# arduinoHeader.net
KiCad netlist of a schematic drawn in Altium Designer
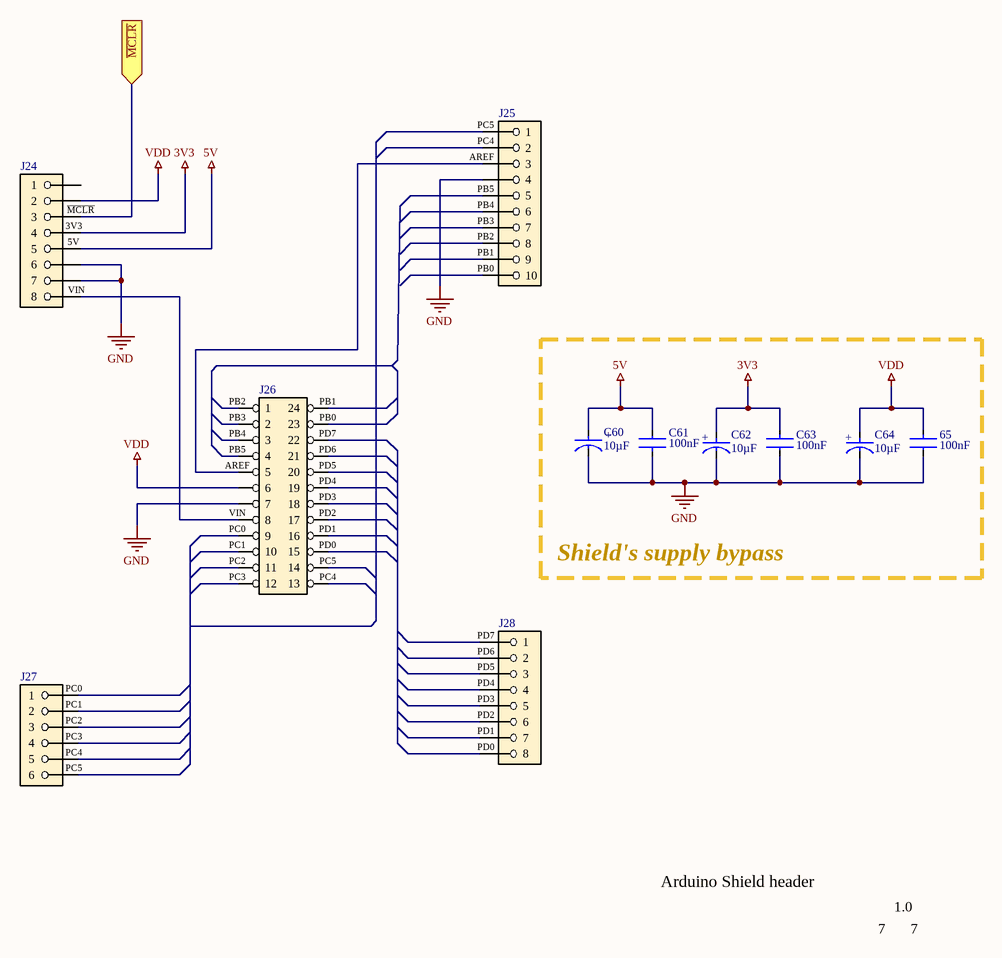
[diagram p0: arduinoHeader.SchDoc]

(export (version "E")
  (design (tool "Eeschema 10.0.6"))
  (components
    (comp (ref "65")
      (value "100nF")
      (footprint "FP-C0805C-DN-MFG")
      (description "CAP CER 1000PF 50V C0G/NP0 0805")
      (fields
        (field (name "MANUFACTURER") "KEMET")
        (field (name "OCTOPART") "https://octopart.com/c0805c102j5gactu-kemet-97757")
      )
      (libsource (lib "Altium Content Vault") (part "b4654b650e69147ec39a6b967a45e02"))
    )
    (comp (ref "C60")
      (value "F981C106MSAAS1")
      (footprint "FP-F98S-MFG")
      (description "CAP TANT 10UF 20% 16V 0805")
      (fields
        (field (name "TOLERANCE") "20%")
        (field (name "CAPACITANCE") "10µF")
        (field (name "OCTOPART") "https://octopart.com/f981c106msaas1-avx-49645945")
      )
      (libsource (lib "Altium Content Vault") (part "cf48714ba7e38822c1575c7ec0b6d1f"))
    )
    (comp (ref "C61")
      (value "100nF")
      (footprint "FP-C0805C-DN-MFG")
      (description "CAP CER 1000PF 50V C0G/NP0 0805")
      (fields
        (field (name "MANUFACTURER") "KEMET")
        (field (name "OCTOPART") "https://octopart.com/c0805c102j5gactu-kemet-97757")
      )
      (libsource (lib "Altium Content Vault") (part "b4654b650e69147ec39a6b967a45e02"))
    )
    (comp (ref "C62")
      (value "F981C106MSAAS1")
      (footprint "FP-F98S-MFG")
      (description "CAP TANT 10UF 20% 16V 0805")
      (fields
        (field (name "TOLERANCE") "20%")
        (field (name "CAPACITANCE") "10µF")
        (field (name "OCTOPART") "https://octopart.com/f981c106msaas1-avx-49645945")
      )
      (libsource (lib "Altium Content Vault") (part "cf48714ba7e38822c1575c7ec0b6d1f"))
    )
    (comp (ref "C63")
      (value "100nF")
      (footprint "FP-C0805C-DN-MFG")
      (description "CAP CER 1000PF 50V C0G/NP0 0805")
      (fields
        (field (name "MANUFACTURER") "KEMET")
        (field (name "OCTOPART") "https://octopart.com/c0805c102j5gactu-kemet-97757")
      )
      (libsource (lib "Altium Content Vault") (part "b4654b650e69147ec39a6b967a45e02"))
    )
    (comp (ref "C64")
      (value "F981C106MSAAS1")
      (footprint "FP-F98S-MFG")
      (description "CAP TANT 10UF 20% 16V 0805")
      (fields
        (field (name "TOLERANCE") "20%")
        (field (name "CAPACITANCE") "10µF")
        (field (name "OCTOPART") "https://octopart.com/f981c106msaas1-avx-49645945")
      )
      (libsource (lib "Altium Content Vault") (part "cf48714ba7e38822c1575c7ec0b6d1f"))
    )
    (comp (ref "J24")
      (value "Header 1x8 F")
      (footprint "Header 1x8")
      (libsource (lib "") (part "Header 1x8 F_1"))
    )
    (comp (ref "J25")
      (value "Header 1x10 F")
      (footprint "Header 1x10")
      (libsource (lib "goldpin") (part "Header 1x10 F"))
    )
    (comp (ref "J26")
      (value "Header 2x12")
      (footprint "Header 2x12")
      (libsource (lib "goldpin") (part "Header 2x12"))
    )
    (comp (ref "J27")
      (value "Header 1x6 F")
      (footprint "Header 1x6")
      (libsource (lib "goldpin") (part "Header 1x6 F"))
    )
    (comp (ref "J28")
      (value "Header 1x8 F")
      (footprint "Header 1x8")
      (libsource (lib "goldpin") (part "Header 1x8 F"))
    )
  )
  (nets
    (net (code "1") (name "/AREF") (class "Default")
      (node (ref "J25") (pin "3") (pinfunction "3_3") (pintype "passive"))
      (node (ref "J26") (pin "5") (pinfunction "5_5") (pintype "passive"))
    )
    (net (code "2") (name "/PB0") (class "Default")
      (node (ref "J25") (pin "10") (pinfunction "10_10") (pintype "passive"))
      (node (ref "J26") (pin "23") (pinfunction "23_23") (pintype "passive"))
    )
    (net (code "3") (name "/PB1") (class "Default")
      (node (ref "J25") (pin "9") (pinfunction "9_9") (pintype "passive"))
      (node (ref "J26") (pin "24") (pinfunction "24_24") (pintype "passive"))
    )
    (net (code "4") (name "/PB2") (class "Default")
      (node (ref "J25") (pin "8") (pinfunction "8_8") (pintype "passive"))
      (node (ref "J26") (pin "1") (pinfunction "1_1") (pintype "passive"))
    )
    (net (code "5") (name "/PB3") (class "Default")
      (node (ref "J25") (pin "7") (pinfunction "7_7") (pintype "passive"))
      (node (ref "J26") (pin "2") (pinfunction "2_2") (pintype "passive"))
    )
    (net (code "6") (name "/PB4") (class "Default")
      (node (ref "J25") (pin "6") (pinfunction "6_6") (pintype "passive"))
      (node (ref "J26") (pin "3") (pinfunction "3_3") (pintype "passive"))
    )
    (net (code "7") (name "/PB5") (class "Default")
      (node (ref "J25") (pin "5") (pinfunction "5_5") (pintype "passive"))
      (node (ref "J26") (pin "4") (pinfunction "4_4") (pintype "passive"))
    )
    (net (code "8") (name "/PC0") (class "Default")
      (node (ref "J26") (pin "9") (pinfunction "9_9") (pintype "passive"))
      (node (ref "J27") (pin "1") (pinfunction "1_1") (pintype "passive"))
    )
    (net (code "9") (name "/PC1") (class "Default")
      (node (ref "J26") (pin "10") (pinfunction "10_10") (pintype "passive"))
      (node (ref "J27") (pin "2") (pinfunction "2_2") (pintype "passive"))
    )
    (net (code "10") (name "/PC2") (class "Default")
      (node (ref "J26") (pin "11") (pinfunction "11_11") (pintype "passive"))
      (node (ref "J27") (pin "3") (pinfunction "3_3") (pintype "passive"))
    )
    (net (code "11") (name "/PC3") (class "Default")
      (node (ref "J26") (pin "12") (pinfunction "12_12") (pintype "passive"))
      (node (ref "J27") (pin "4") (pinfunction "4_4") (pintype "passive"))
    )
    (net (code "12") (name "/PC4") (class "Default")
      (node (ref "J25") (pin "2") (pinfunction "2_2") (pintype "passive"))
      (node (ref "J26") (pin "13") (pinfunction "13_13") (pintype "passive"))
      (node (ref "J27") (pin "5") (pinfunction "5_5") (pintype "passive"))
    )
    (net (code "13") (name "/PC5") (class "Default")
      (node (ref "J25") (pin "1") (pinfunction "1_1") (pintype "passive"))
      (node (ref "J26") (pin "14") (pinfunction "14_14") (pintype "passive"))
      (node (ref "J27") (pin "6") (pinfunction "6_6") (pintype "passive"))
    )
    (net (code "14") (name "/PD0") (class "Default")
      (node (ref "J26") (pin "15") (pinfunction "15_15") (pintype "passive"))
      (node (ref "J28") (pin "8") (pinfunction "8_8") (pintype "passive"))
    )
    (net (code "15") (name "/PD1") (class "Default")
      (node (ref "J26") (pin "16") (pinfunction "16_16") (pintype "passive"))
      (node (ref "J28") (pin "7") (pinfunction "7_7") (pintype "passive"))
    )
    (net (code "16") (name "/PD2") (class "Default")
      (node (ref "J26") (pin "17") (pinfunction "17_17") (pintype "passive"))
      (node (ref "J28") (pin "6") (pinfunction "6_6") (pintype "passive"))
    )
    (net (code "17") (name "/PD3") (class "Default")
      (node (ref "J26") (pin "18") (pinfunction "18_18") (pintype "passive"))
      (node (ref "J28") (pin "5") (pinfunction "5_5") (pintype "passive"))
    )
    (net (code "18") (name "/PD4") (class "Default")
      (node (ref "J26") (pin "19") (pinfunction "19_19") (pintype "passive"))
      (node (ref "J28") (pin "4") (pinfunction "4_4") (pintype "passive"))
    )
    (net (code "19") (name "/PD5") (class "Default")
      (node (ref "J26") (pin "20") (pinfunction "20_20") (pintype "passive"))
      (node (ref "J28") (pin "3") (pinfunction "3_3") (pintype "passive"))
    )
    (net (code "20") (name "/PD6") (class "Default")
      (node (ref "J26") (pin "21") (pinfunction "21_21") (pintype "passive"))
      (node (ref "J28") (pin "2") (pinfunction "2_2") (pintype "passive"))
    )
    (net (code "21") (name "/PD7") (class "Default")
      (node (ref "J26") (pin "22") (pinfunction "22_22") (pintype "passive"))
      (node (ref "J28") (pin "1") (pinfunction "1_1") (pintype "passive"))
    )
    (net (code "22") (name "/VIN") (class "Default")
      (node (ref "J24") (pin "8") (pinfunction "8_8") (pintype "passive"))
      (node (ref "J26") (pin "8") (pinfunction "8_8") (pintype "passive"))
    )
    (net (code "23") (name "/~{MCLR}") (class "Default")
      (node (ref "J24") (pin "3") (pinfunction "3_3") (pintype "passive"))
    )
    (net (code "24") (name "3V3") (class "Default")
      (node (ref "C62") (pin "2") (pinfunction "A_2") (pintype "passive"))
      (node (ref "C63") (pin "1") (pinfunction "1_1") (pintype "passive"))
      (node (ref "J24") (pin "4") (pinfunction "4_4") (pintype "passive"))
    )
    (net (code "25") (name "5V") (class "Default")
      (node (ref "C60") (pin "2") (pinfunction "A_2") (pintype "passive"))
      (node (ref "C61") (pin "2") (pinfunction "2_2") (pintype "passive"))
      (node (ref "J24") (pin "5") (pinfunction "5_5") (pintype "passive"))
    )
    (net (code "26") (name "GND") (class "Default")
      (node (ref "65") (pin "2") (pinfunction "2_2") (pintype "passive"))
      (node (ref "C60") (pin "1") (pinfunction "C_1") (pintype "passive"))
      (node (ref "C61") (pin "1") (pinfunction "1_1") (pintype "passive"))
      (node (ref "C62") (pin "1") (pinfunction "C_1") (pintype "passive"))
      (node (ref "C63") (pin "2") (pinfunction "2_2") (pintype "passive"))
      (node (ref "C64") (pin "1") (pinfunction "C_1") (pintype "passive"))
      (node (ref "J24") (pin "6") (pinfunction "6_6") (pintype "passive"))
      (node (ref "J24") (pin "7") (pinfunction "7_7") (pintype "passive"))
      (node (ref "J25") (pin "4") (pinfunction "4_4") (pintype "passive"))
      (node (ref "J26") (pin "7") (pinfunction "7_7") (pintype "passive"))
    )
    (net (code "27") (name "VDD") (class "Default")
      (node (ref "65") (pin "1") (pinfunction "1_1") (pintype "passive"))
      (node (ref "C64") (pin "2") (pinfunction "A_2") (pintype "passive"))
      (node (ref "J24") (pin "2") (pinfunction "2_2") (pintype "passive"))
      (node (ref "J26") (pin "6") (pinfunction "6_6") (pintype "passive"))
    )
    (net (code "28") (name "unconnected-(J24-Pad1)") (class "Default")
      (node (ref "J24") (pin "1") (pinfunction "1_1") (pintype "passive"))
    )
  )
)
